# motorControl.net
KiCad netlist of a schematic drawn in EAGLE
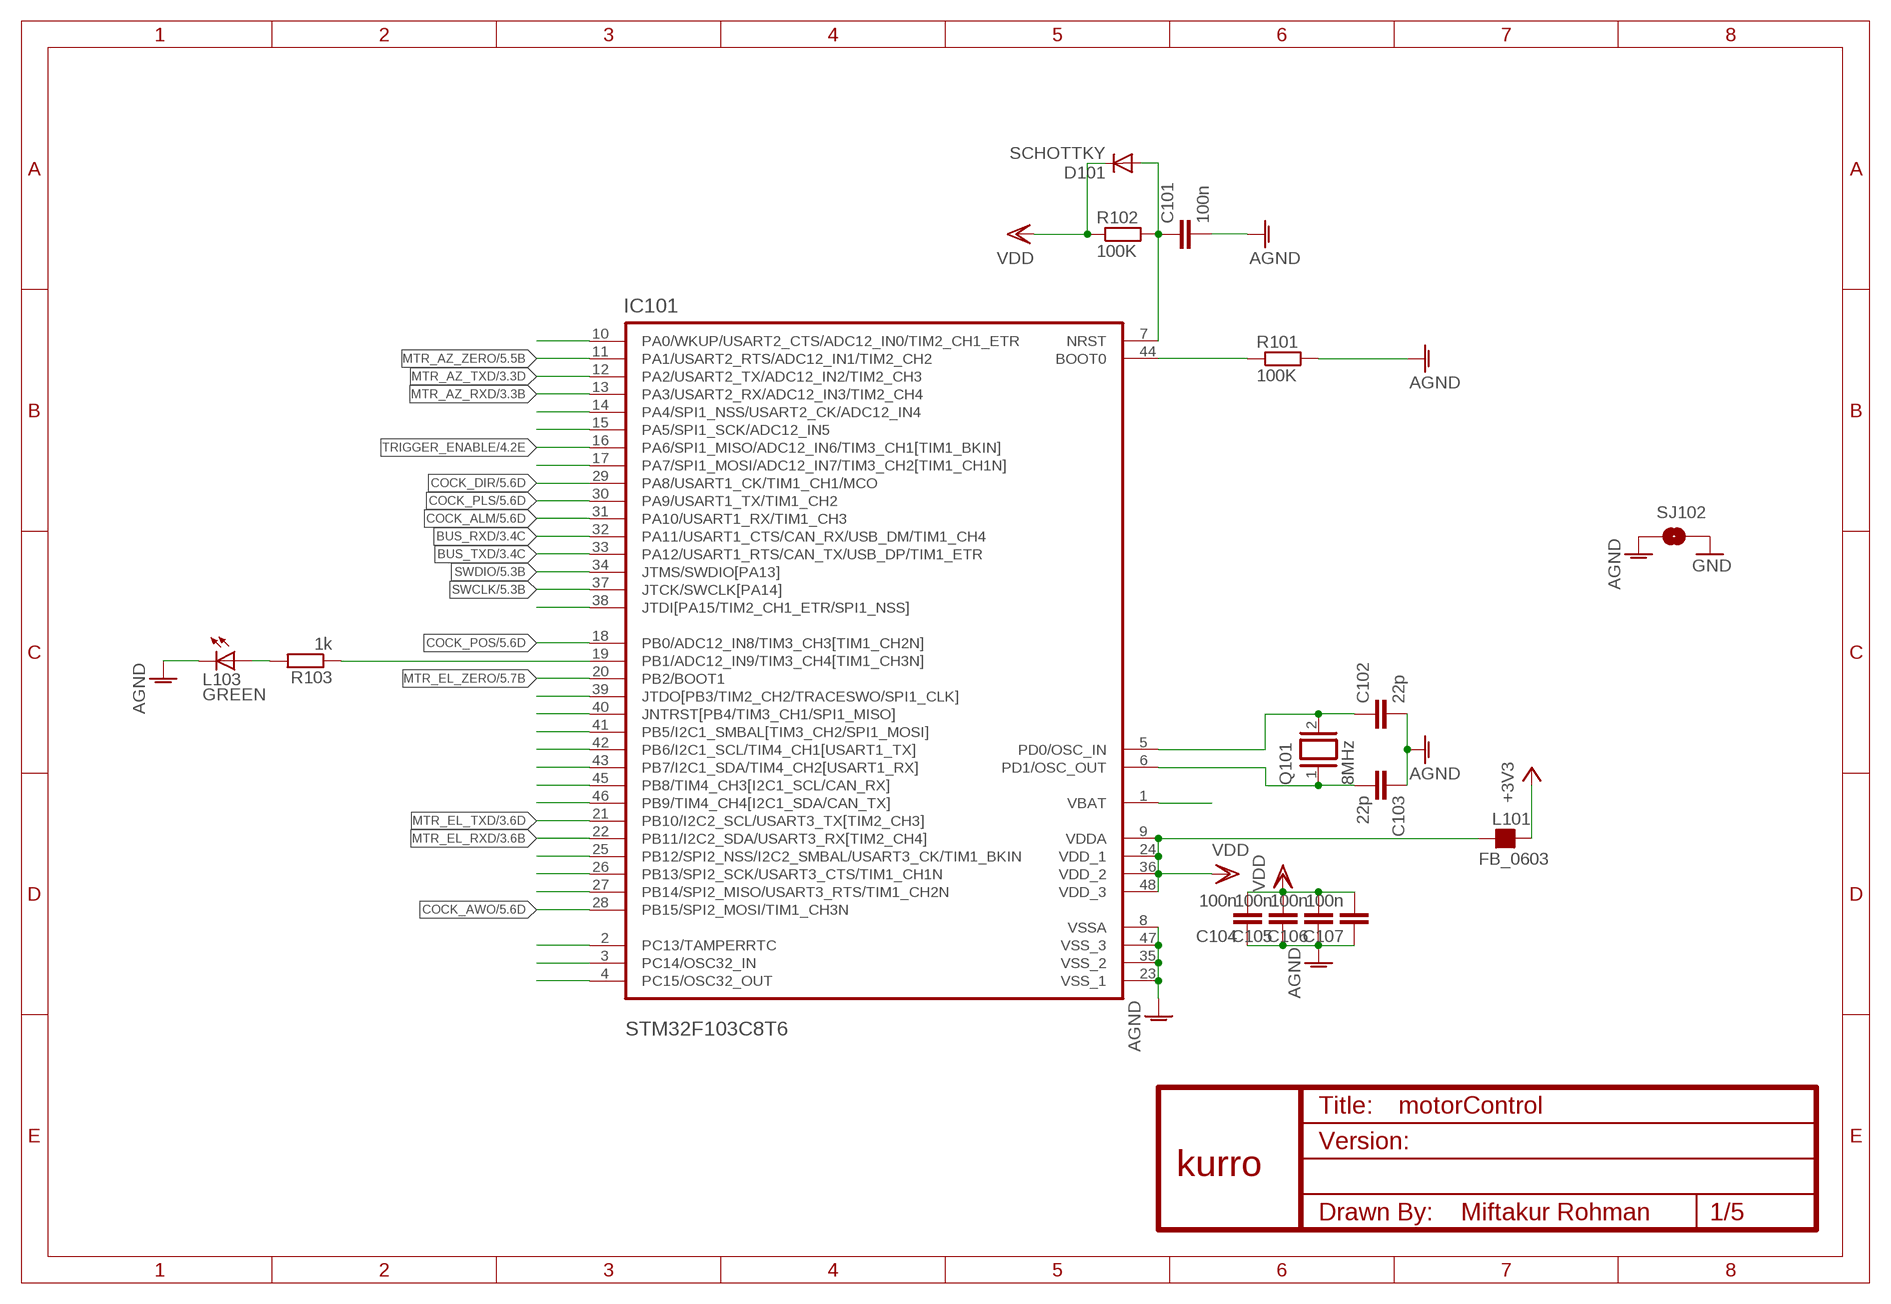
[diagram p0: schematic, sheet 1]
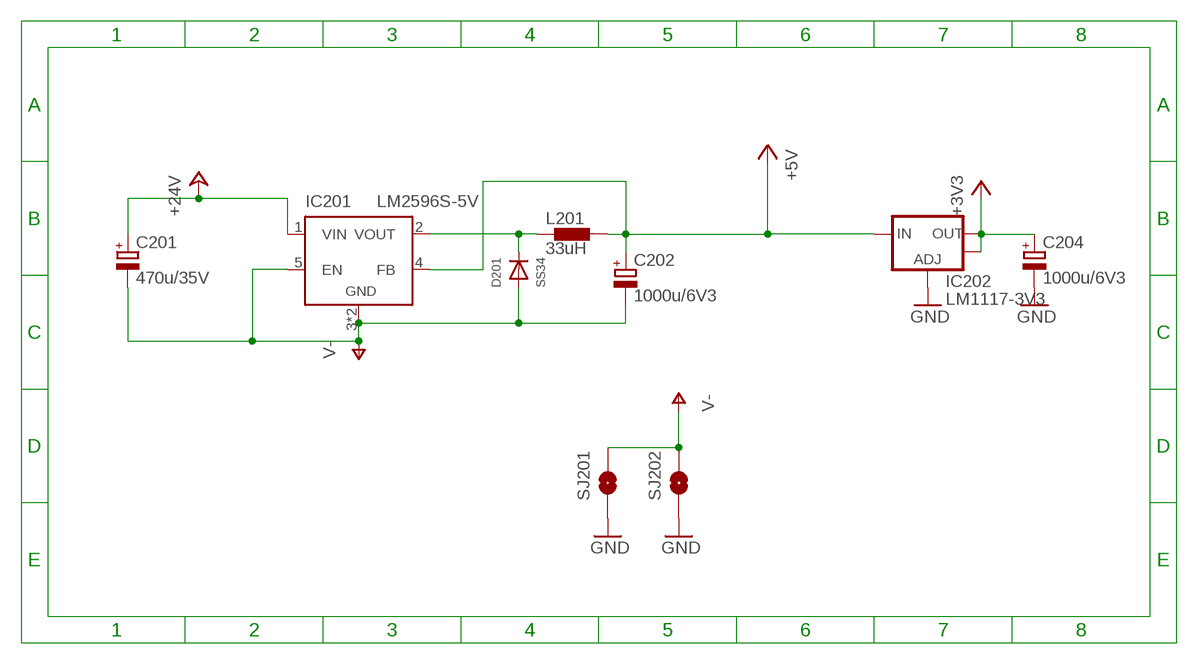
[diagram p1: schematic, sheet 2]
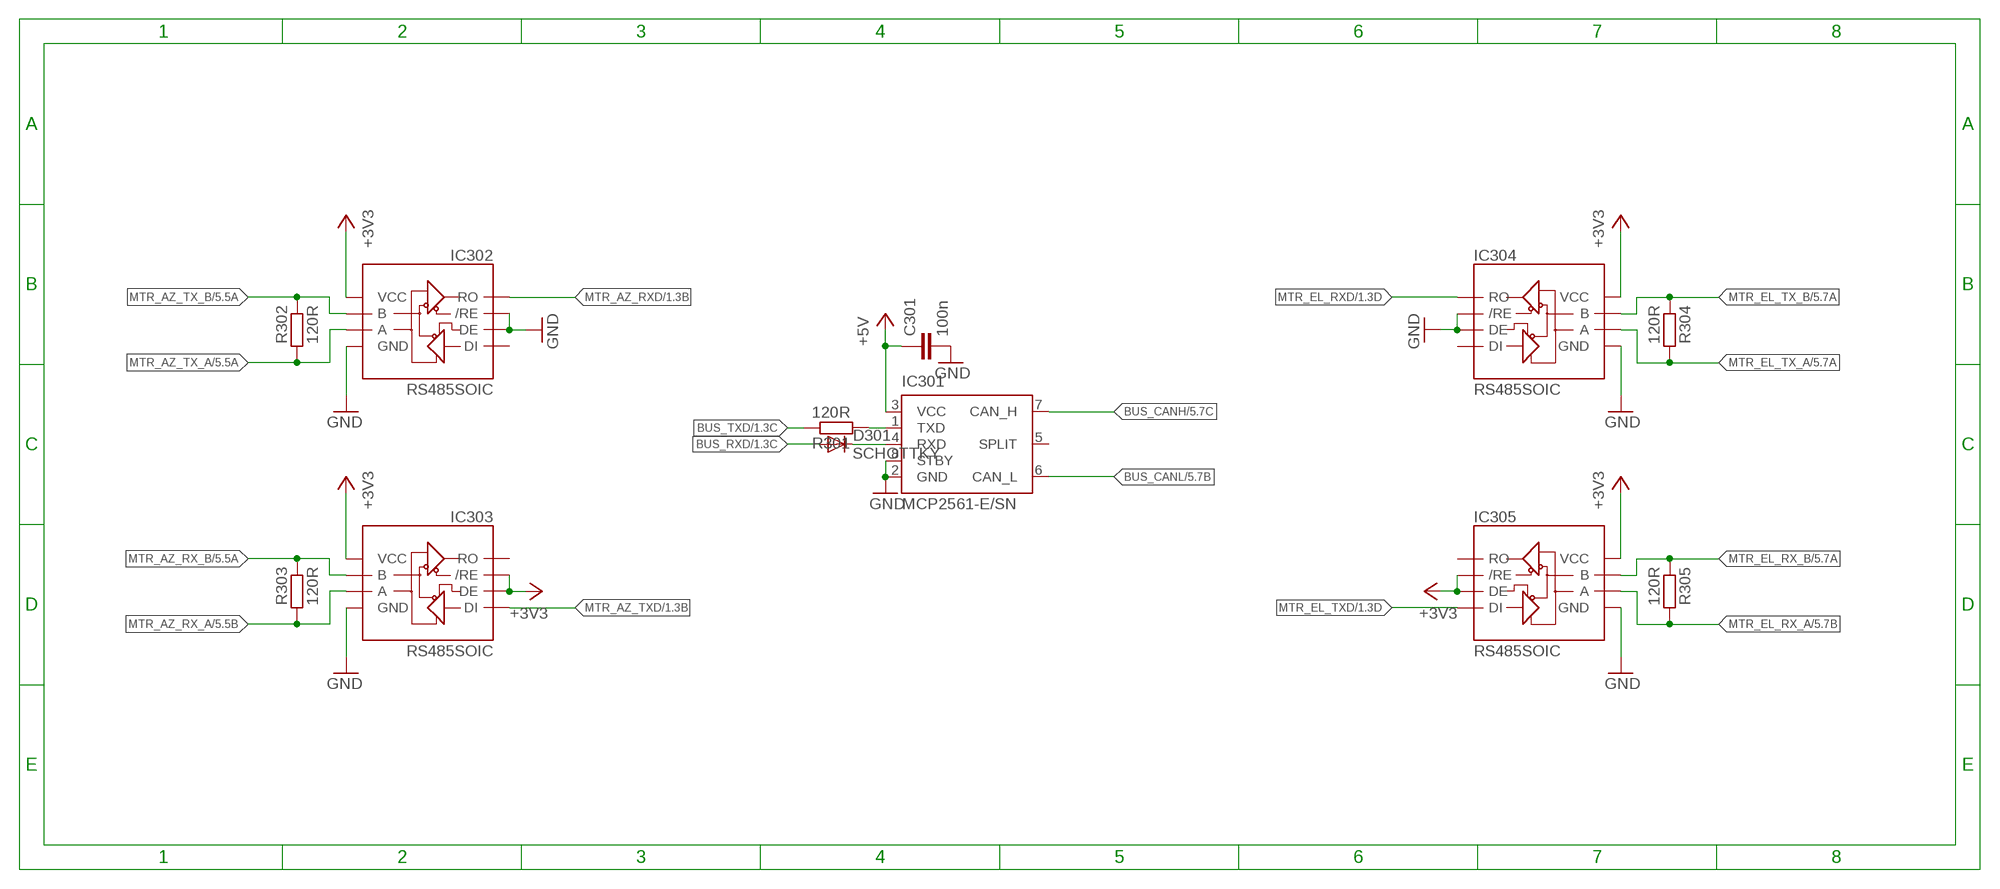
[diagram p2: schematic, sheet 3]
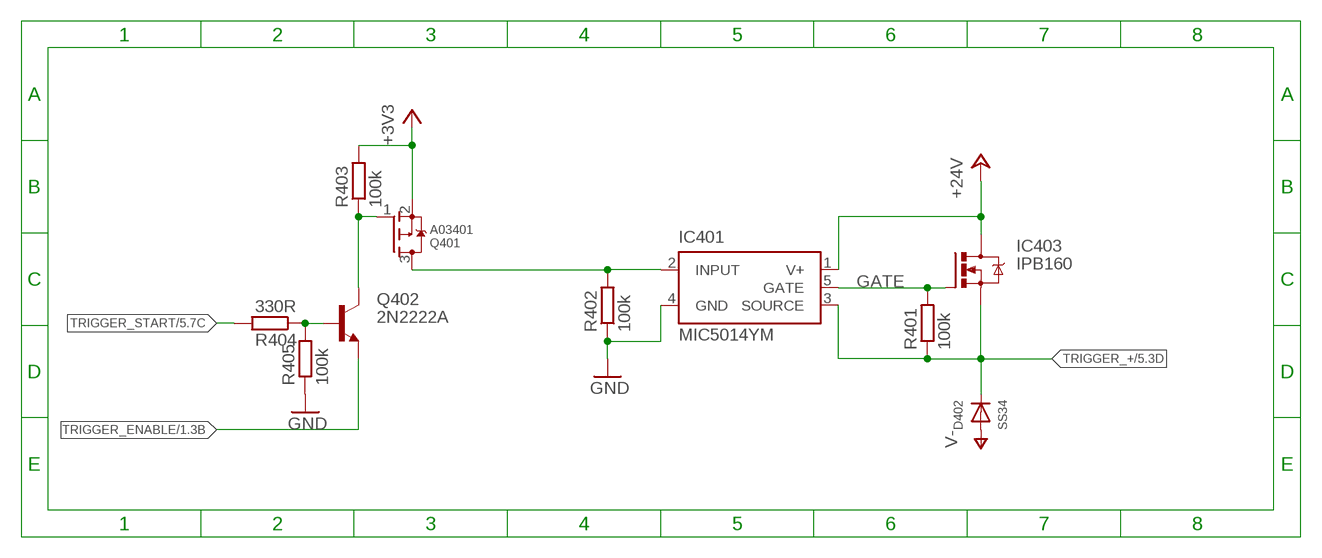
[diagram p3: schematic, sheet 4]
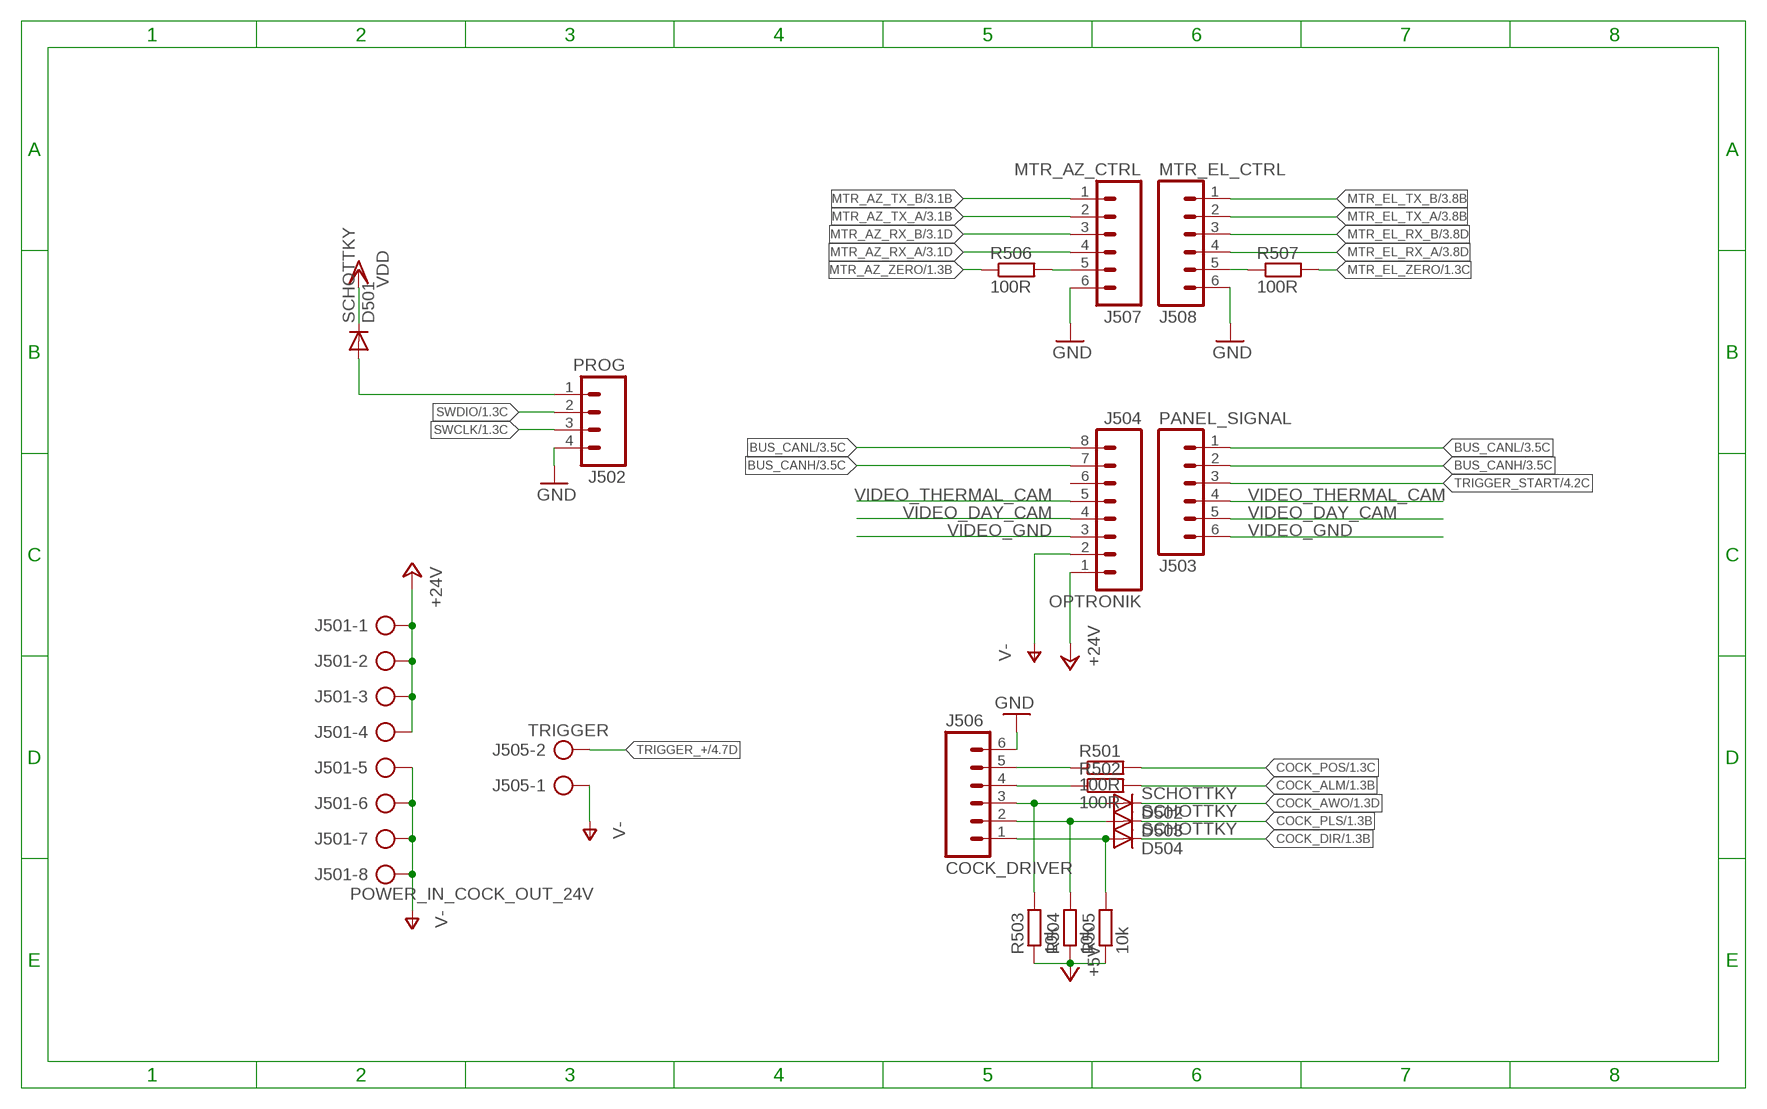
[diagram p4: schematic, sheet 5]

(export (version "E")
  (design (tool "Eeschema 10.0.6"))
  (components
    (comp (ref "C101")
      (value "100n")
      (footprint "eagle-import:C0603")
      (libsource (lib "eagle-import") (part "resistor_C-EUC0603"))
    )
    (comp (ref "C102")
      (value "22p")
      (footprint "eagle-import:C0603")
      (libsource (lib "eagle-import") (part "resistor_C-EUC0603"))
    )
    (comp (ref "C103")
      (value "22p")
      (footprint "eagle-import:C0603")
      (libsource (lib "eagle-import") (part "resistor_C-EUC0603"))
    )
    (comp (ref "C104")
      (value "100n")
      (footprint "eagle-import:C0603")
      (libsource (lib "eagle-import") (part "resistor_C-EUC0603"))
    )
    (comp (ref "C105")
      (value "100n")
      (footprint "eagle-import:C0603")
      (libsource (lib "eagle-import") (part "resistor_C-EUC0603"))
    )
    (comp (ref "C106")
      (value "100n")
      (footprint "eagle-import:C0603")
      (libsource (lib "eagle-import") (part "resistor_C-EUC0603"))
    )
    (comp (ref "C107")
      (value "100n")
      (footprint "eagle-import:C0603")
      (libsource (lib "eagle-import") (part "resistor_C-EUC0603"))
    )
    (comp (ref "D101")
      (value "SCHOTTKY")
      (footprint "eagle-import:MICROMELF-W")
      (libsource (lib "eagle-import") (part "DIODE-MICROMELF-W"))
    )
    (comp (ref "IC101")
      (value "STM32F103C8T6")
      (footprint "eagle-import:QFP50P900X900X160-48N")
      (fields (field (name "MPN") "STM32F103CBT6"))
      (libsource (lib "eagle-import") (part "STM32F103C8T6"))
    )
    (comp (ref "L101")
      (value "FB_0603")
      (footprint "eagle-import:L0603")
      (libsource (lib "eagle-import") (part "FB_0603"))
    )
    (comp (ref "L103")
      (value "GREEN")
      (footprint "eagle-import:CHIP-LED0805")
      (libsource (lib "eagle-import") (part "LEDCHIP-LED0805"))
    )
    (comp (ref "Q101")
      (value "8MHz")
      (footprint "eagle-import:QS")
      (libsource (lib "eagle-import") (part "XTAL/S"))
    )
    (comp (ref "R101")
      (value "100K")
      (footprint "eagle-import:R0603")
      (libsource (lib "eagle-import") (part "resistor_R-EU_R0603"))
    )
    (comp (ref "R102")
      (value "100K")
      (footprint "eagle-import:R0603")
      (libsource (lib "eagle-import") (part "resistor_R-EU_R0603"))
    )
    (comp (ref "R103")
      (value "1k")
      (footprint "eagle-import:R0603")
      (libsource (lib "eagle-import") (part "resistor_R-EU_R0603"))
    )
    (comp (ref "SJ102")
      (value "SOLDERJUMPERTRACE")
      (footprint "eagle-import:SJ_2S-TRACE")
      (libsource (lib "eagle-import") (part "SOLDERJUMPERTRACE"))
    )
    (comp (ref "U$1")
      (value "KURRO_FOOTPRINT")
      (footprint "eagle-import:KURRO-LOGO")
      (libsource (lib "eagle-import") (part "KURRO_FOOTPRINT"))
    )
    (comp (ref "C301")
      (value "100n")
      (footprint "eagle-import:C0603")
      (libsource (lib "eagle-import") (part "C-EUC0603"))
    )
    (comp (ref "D301")
      (value "SCHOTTKY")
      (footprint "eagle-import:MICROMELF-W")
      (libsource (lib "eagle-import") (part "DIODE-MICROMELF-W"))
    )
    (comp (ref "IC301")
      (value "MCP2561-E/SN")
      (footprint "eagle-import:SOIC-8")
      (libsource (lib "eagle-import") (part "MCP2561-E/SN"))
    )
    (comp (ref "IC302")
      (value "RS485SOIC")
      (footprint "eagle-import:SO08")
      (libsource (lib "eagle-import") (part "RS485SOIC"))
    )
    (comp (ref "IC303")
      (value "RS485SOIC")
      (footprint "eagle-import:SO08")
      (libsource (lib "eagle-import") (part "RS485SOIC"))
    )
    (comp (ref "IC304")
      (value "RS485SOIC")
      (footprint "eagle-import:SO08")
      (libsource (lib "eagle-import") (part "RS485SOIC"))
    )
    (comp (ref "IC305")
      (value "RS485SOIC")
      (footprint "eagle-import:SO08")
      (libsource (lib "eagle-import") (part "RS485SOIC"))
    )
    (comp (ref "R301")
      (value "120R")
      (footprint "eagle-import:R0603")
      (libsource (lib "eagle-import") (part "resistor_R-EU_R0603"))
    )
    (comp (ref "R302")
      (value "120R")
      (footprint "eagle-import:R0603")
      (libsource (lib "eagle-import") (part "resistor_R-EU_R0603"))
    )
    (comp (ref "R303")
      (value "120R")
      (footprint "eagle-import:R0603")
      (libsource (lib "eagle-import") (part "resistor_R-EU_R0603"))
    )
    (comp (ref "R304")
      (value "120R")
      (footprint "eagle-import:R0603")
      (libsource (lib "eagle-import") (part "resistor_R-EU_R0603"))
    )
    (comp (ref "R305")
      (value "120R")
      (footprint "eagle-import:R0603")
      (libsource (lib "eagle-import") (part "resistor_R-EU_R0603"))
    )
    (comp (ref "C201")
      (value "470u/35V")
      (footprint "eagle-import:153CLV-1012")
      (libsource (lib "eagle-import") (part "CPOL-EU153CLV-1012"))
    )
    (comp (ref "C202")
      (value "1000u/6V3")
      (footprint "eagle-import:153CLV-0810")
      (libsource (lib "eagle-import") (part "CPOL-EU153CLV-0810"))
    )
    (comp (ref "C204")
      (value "1000u/6V3")
      (footprint "eagle-import:153CLV-0810")
      (libsource (lib "eagle-import") (part "CPOL-EU153CLV-0810"))
    )
    (comp (ref "D201")
      (value "SS34")
      (footprint "eagle-import:SMADIODE")
      (libsource (lib "eagle-import") (part "DIODESMA"))
    )
    (comp (ref "IC201")
      (value "LM2596S-5V")
      (footprint "eagle-import:D2PAK")
      (libsource (lib "eagle-import") (part "LM2596S-ADJ"))
    )
    (comp (ref "IC202")
      (value "LM1117-3V3")
      (footprint "eagle-import:SOT223")
      (libsource (lib "eagle-import") (part "V_REG_LM1117SOT223"))
    )
    (comp (ref "L201")
      (value "33uH")
      (footprint "eagle-import:PA4342")
      (libsource (lib "eagle-import") (part "PA4342"))
    )
    (comp (ref "SJ201")
      (value "SOLDERJUMPERTRACE")
      (footprint "eagle-import:SJ_2S-TRACE")
      (libsource (lib "eagle-import") (part "SOLDERJUMPERTRACE"))
    )
    (comp (ref "SJ202")
      (value "SOLDERJUMPERTRACE")
      (footprint "eagle-import:SJ_2S-TRACE")
      (libsource (lib "eagle-import") (part "SOLDERJUMPERTRACE"))
    )
    (comp (ref "D402")
      (value "SS34")
      (footprint "eagle-import:SMADIODE")
      (libsource (lib "eagle-import") (part "DIODESMA"))
    )
    (comp (ref "IC401")
      (value "MIC5014YM")
      (footprint "eagle-import:SO-08")
      (libsource (lib "eagle-import") (part "MIC501M4Y"))
    )
    (comp (ref "IC403")
      (value "IPB160")
      (footprint "eagle-import:PG-TO263-7")
      (libsource (lib "eagle-import") (part "IPB160"))
    )
    (comp (ref "Q401")
      (value "A03401")
      (footprint "eagle-import:SOT23")
      (libsource (lib "eagle-import") (part "A03401-REFLOW"))
    )
    (comp (ref "Q402")
      (value "2N2222A")
      (footprint "eagle-import:SOT23")
      (libsource (lib "eagle-import") (part "2N2222-REFLOWA"))
    )
    (comp (ref "R401")
      (value "100k")
      (footprint "eagle-import:R0603")
      (libsource (lib "eagle-import") (part "R-EU_R0603"))
    )
    (comp (ref "R402")
      (value "100k")
      (footprint "eagle-import:R0603")
      (libsource (lib "eagle-import") (part "R-EU_R0603"))
    )
    (comp (ref "R403")
      (value "100k")
      (footprint "eagle-import:R0603")
      (libsource (lib "eagle-import") (part "R-EU_R0603"))
    )
    (comp (ref "R404")
      (value "330R")
      (footprint "eagle-import:R0603")
      (libsource (lib "eagle-import") (part "R-EU_R0603"))
    )
    (comp (ref "R405")
      (value "100k")
      (footprint "eagle-import:R0603")
      (libsource (lib "eagle-import") (part "R-EU_R0603"))
    )
    (comp (ref "D501")
      (value "SCHOTTKY")
      (footprint "eagle-import:MICROMELF-W")
      (libsource (lib "eagle-import") (part "DIODE-MICROMELF-W"))
    )
    (comp (ref "D502")
      (value "SCHOTTKY")
      (footprint "eagle-import:MICROMELF-W")
      (libsource (lib "eagle-import") (part "DIODE-MICROMELF-W"))
    )
    (comp (ref "D503")
      (value "SCHOTTKY")
      (footprint "eagle-import:MICROMELF-W")
      (libsource (lib "eagle-import") (part "DIODE-MICROMELF-W"))
    )
    (comp (ref "D504")
      (value "SCHOTTKY")
      (footprint "eagle-import:MICROMELF-W")
      (libsource (lib "eagle-import") (part "DIODE-MICROMELF-W"))
    )
    (comp (ref "J501")
      (value "POWER_IN_COCK_OUT_24V")
      (footprint "eagle-import:AK300_8")
      (libsource (lib "eagle-import") (part "AK300/8"))
    )
    (comp (ref "J502")
      (value "PROG")
      (footprint "eagle-import:XH-4-VERT-SMD")
      (libsource (lib "eagle-import") (part "M04-XH-VERT-SMD"))
    )
    (comp (ref "J503")
      (value "PANEL_SIGNAL")
      (footprint "eagle-import:XH-6-VERT-SMD")
      (libsource (lib "eagle-import") (part "M06-XH-VERT-SMD"))
    )
    (comp (ref "J504")
      (value "OPTRONIK")
      (footprint "eagle-import:XH-8-VERT-SMD")
      (libsource (lib "eagle-import") (part "M08-XH-VERT-SMD"))
    )
    (comp (ref "J505")
      (value "TRIGGER")
      (footprint "eagle-import:AK300_2")
      (libsource (lib "eagle-import") (part "AK300/2"))
    )
    (comp (ref "J506")
      (value "COCK_DRIVER")
      (footprint "eagle-import:XH-6-VERT-SMD")
      (libsource (lib "eagle-import") (part "M06-XH-VERT-SMD"))
    )
    (comp (ref "J507")
      (value "MTR_AZ_CTRL")
      (footprint "eagle-import:XH-6-VERT-SMD")
      (libsource (lib "eagle-import") (part "M06-XH-VERT-SMD"))
    )
    (comp (ref "J508")
      (value "MTR_EL_CTRL")
      (footprint "eagle-import:XH-6-VERT-SMD")
      (libsource (lib "eagle-import") (part "M06-XH-VERT-SMD"))
    )
    (comp (ref "R501")
      (value "100R")
      (footprint "eagle-import:R0603")
      (libsource (lib "eagle-import") (part "resistor_R-EU_R0603"))
    )
    (comp (ref "R502")
      (value "100R")
      (footprint "eagle-import:R0603")
      (libsource (lib "eagle-import") (part "resistor_R-EU_R0603"))
    )
    (comp (ref "R503")
      (value "10k")
      (footprint "eagle-import:R0603")
      (libsource (lib "eagle-import") (part "resistor_R-EU_R0603"))
    )
    (comp (ref "R504")
      (value "10k")
      (footprint "eagle-import:R0603")
      (libsource (lib "eagle-import") (part "resistor_R-EU_R0603"))
    )
    (comp (ref "R505")
      (value "10k")
      (footprint "eagle-import:R0603")
      (libsource (lib "eagle-import") (part "resistor_R-EU_R0603"))
    )
    (comp (ref "R506")
      (value "100R")
      (footprint "eagle-import:R0603")
      (libsource (lib "eagle-import") (part "resistor_R-EU_R0603"))
    )
    (comp (ref "R507")
      (value "100R")
      (footprint "eagle-import:R0603")
      (libsource (lib "eagle-import") (part "resistor_R-EU_R0603"))
    )
  )
  (nets
    (net (code "1") (name "+3V3") (class "Default")
      (node (ref "C204") (pin "+") (pinfunction "+_+") (pintype "passive"))
      (node (ref "IC202") (pin "2") (pinfunction "OUT_2") (pintype "power_in"))
      (node (ref "IC202") (pin "4") (pinfunction "OUT_4") (pintype "power_in"))
      (node (ref "IC302") (pin "8") (pinfunction "VCC_8") (pintype "bidirectional"))
      (node (ref "IC303") (pin "2") (pinfunction "/RE_2") (pintype "bidirectional"))
      (node (ref "IC303") (pin "3") (pinfunction "DE_3") (pintype "bidirectional"))
      (node (ref "IC303") (pin "8") (pinfunction "VCC_8") (pintype "bidirectional"))
      (node (ref "IC304") (pin "8") (pinfunction "VCC_8") (pintype "bidirectional"))
      (node (ref "IC305") (pin "2") (pinfunction "/RE_2") (pintype "bidirectional"))
      (node (ref "IC305") (pin "3") (pinfunction "DE_3") (pintype "bidirectional"))
      (node (ref "IC305") (pin "8") (pinfunction "VCC_8") (pintype "bidirectional"))
      (node (ref "L101") (pin "2") (pinfunction "2_2") (pintype "passive"))
      (node (ref "Q401") (pin "2") (pinfunction "S_2") (pintype "bidirectional"))
      (node (ref "R403") (pin "2") (pinfunction "2_2") (pintype "passive"))
    )
    (net (code "2") (name "+5V") (class "Default")
      (node (ref "C202") (pin "+") (pinfunction "+_+") (pintype "passive"))
      (node (ref "C301") (pin "1") (pinfunction "1_1") (pintype "passive"))
      (node (ref "IC201") (pin "4") (pinfunction "FB_4") (pintype "input"))
      (node (ref "IC202") (pin "3") (pinfunction "IN_3") (pintype "input"))
      (node (ref "IC301") (pin "3") (pinfunction "VCC_3") (pintype "bidirectional"))
      (node (ref "L201") (pin "P$2") (pinfunction "2_P$2") (pintype "passive"))
      (node (ref "R503") (pin "1") (pinfunction "1_1") (pintype "passive"))
      (node (ref "R504") (pin "1") (pinfunction "1_1") (pintype "passive"))
      (node (ref "R505") (pin "1") (pinfunction "1_1") (pintype "passive"))
    )
    (net (code "3") (name "+24V") (class "Default")
      (node (ref "C201") (pin "+") (pinfunction "+_+") (pintype "passive"))
      (node (ref "IC201") (pin "1") (pinfunction "VIN_1") (pintype "power_in"))
      (node (ref "IC401") (pin "1") (pinfunction "V+_1") (pintype "bidirectional"))
      (node (ref "IC403") (pin "4") (pinfunction "D_4") (pintype "passive"))
      (node (ref "J501") (pin "1") (pinfunction "KL_1") (pintype "passive"))
      (node (ref "J501") (pin "2") (pinfunction "KL_2") (pintype "passive"))
      (node (ref "J501") (pin "3") (pinfunction "KL_3") (pintype "passive"))
      (node (ref "J501") (pin "4") (pinfunction "KL_4") (pintype "passive"))
      (node (ref "J504") (pin "1") (pinfunction "1_1") (pintype "passive"))
    )
    (net (code "4") (name "AGND") (class "Default")
      (node (ref "C101") (pin "2") (pinfunction "2_2") (pintype "passive"))
      (node (ref "C102") (pin "2") (pinfunction "2_2") (pintype "passive"))
      (node (ref "C103") (pin "1") (pinfunction "1_1") (pintype "passive"))
      (node (ref "C104") (pin "1") (pinfunction "1_1") (pintype "passive"))
      (node (ref "C105") (pin "1") (pinfunction "1_1") (pintype "passive"))
      (node (ref "C106") (pin "1") (pinfunction "1_1") (pintype "passive"))
      (node (ref "C107") (pin "1") (pinfunction "1_1") (pintype "passive"))
      (node (ref "IC101") (pin "23") (pinfunction "VSS_1_23") (pintype "bidirectional"))
      (node (ref "IC101") (pin "35") (pinfunction "VSS_2_35") (pintype "passive"))
      (node (ref "IC101") (pin "47") (pinfunction "VSS_3_47") (pintype "passive"))
      (node (ref "IC101") (pin "8") (pinfunction "VSSA_8") (pintype "passive"))
      (node (ref "L103") (pin "C") (pinfunction "C_C") (pintype "passive"))
      (node (ref "R101") (pin "2") (pinfunction "2_2") (pintype "passive"))
      (node (ref "SJ102") (pin "1") (pinfunction "1_1") (pintype "passive"))
    )
    (net (code "5") (name "BUS_CANH") (class "Default")
      (node (ref "IC301") (pin "7") (pinfunction "CAN_H_7") (pintype "bidirectional"))
      (node (ref "J503") (pin "2") (pinfunction "2_2") (pintype "passive"))
      (node (ref "J504") (pin "7") (pinfunction "7_7") (pintype "passive"))
    )
    (net (code "6") (name "BUS_CANL") (class "Default")
      (node (ref "IC301") (pin "6") (pinfunction "CAN_L_6") (pintype "bidirectional"))
      (node (ref "J503") (pin "1") (pinfunction "1_1") (pintype "passive"))
      (node (ref "J504") (pin "8") (pinfunction "8_8") (pintype "passive"))
    )
    (net (code "7") (name "BUS_RXD") (class "Default")
      (node (ref "D301") (pin "A") (pinfunction "A_A") (pintype "passive"))
      (node (ref "IC101") (pin "32") (pinfunction "PA11/USART1_CTS/CAN_RX/USB_DM/TIM1_CH4_32") (pintype "power_in"))
    )
    (net (code "8") (name "BUS_TXD") (class "Default")
      (node (ref "IC101") (pin "33") (pinfunction "PA12/USART1_RTS/CAN_TX/USB_DP/TIM1_ETR_33") (pintype "bidirectional"))
      (node (ref "R301") (pin "1") (pinfunction "1_1") (pintype "passive"))
    )
    (net (code "9") (name "COCK_ALM") (class "Default")
      (node (ref "IC101") (pin "31") (pinfunction "PA10/USART1_RX/TIM1_CH3_31") (pintype "bidirectional"))
      (node (ref "R502") (pin "2") (pinfunction "2_2") (pintype "passive"))
    )
    (net (code "10") (name "COCK_AWO") (class "Default")
      (node (ref "D502") (pin "C") (pinfunction "C_C") (pintype "passive"))
      (node (ref "IC101") (pin "28") (pinfunction "PB15/SPI2_MOSI/TIM1_CH3N_28") (pintype "bidirectional"))
    )
    (net (code "11") (name "COCK_DIR") (class "Default")
      (node (ref "D504") (pin "C") (pinfunction "C_C") (pintype "passive"))
      (node (ref "IC101") (pin "29") (pinfunction "PA8/USART1_CK/TIM1_CH1/MCO_29") (pintype "bidirectional"))
    )
    (net (code "12") (name "COCK_PLS") (class "Default")
      (node (ref "D503") (pin "C") (pinfunction "C_C") (pintype "passive"))
      (node (ref "IC101") (pin "30") (pinfunction "PA9/USART1_TX/TIM1_CH2_30") (pintype "bidirectional"))
    )
    (net (code "13") (name "COCK_POS") (class "Default")
      (node (ref "IC101") (pin "18") (pinfunction "PB0/ADC12_IN8/TIM3_CH3[TIM1_CH2N]_18") (pintype "bidirectional"))
      (node (ref "R501") (pin "2") (pinfunction "2_2") (pintype "passive"))
    )
    (net (code "14") (name "GATE") (class "Default")
      (node (ref "IC401") (pin "5") (pinfunction "GATE_5") (pintype "bidirectional"))
      (node (ref "IC403") (pin "1") (pinfunction "G_1") (pintype "passive"))
      (node (ref "R401") (pin "2") (pinfunction "2_2") (pintype "passive"))
    )
    (net (code "15") (name "GND") (class "Default")
      (node (ref "C204") (pin "-") (pinfunction "-_-") (pintype "passive"))
      (node (ref "C301") (pin "2") (pinfunction "2_2") (pintype "passive"))
      (node (ref "IC202") (pin "1") (pinfunction "ADJ_1") (pintype "input"))
      (node (ref "IC301") (pin "2") (pinfunction "GND_2") (pintype "bidirectional"))
      (node (ref "IC301") (pin "8") (pinfunction "STBY_8") (pintype "bidirectional"))
      (node (ref "IC302") (pin "2") (pinfunction "/RE_2") (pintype "bidirectional"))
      (node (ref "IC302") (pin "3") (pinfunction "DE_3") (pintype "bidirectional"))
      (node (ref "IC302") (pin "5") (pinfunction "GND_5") (pintype "bidirectional"))
      (node (ref "IC303") (pin "5") (pinfunction "GND_5") (pintype "bidirectional"))
      (node (ref "IC304") (pin "2") (pinfunction "/RE_2") (pintype "bidirectional"))
      (node (ref "IC304") (pin "3") (pinfunction "DE_3") (pintype "bidirectional"))
      (node (ref "IC304") (pin "5") (pinfunction "GND_5") (pintype "bidirectional"))
      (node (ref "IC305") (pin "5") (pinfunction "GND_5") (pintype "bidirectional"))
      (node (ref "IC401") (pin "4") (pinfunction "GND_4") (pintype "bidirectional"))
      (node (ref "J502") (pin "4") (pinfunction "4_4") (pintype "passive"))
      (node (ref "J506") (pin "6") (pinfunction "6_6") (pintype "passive"))
      (node (ref "J507") (pin "6") (pinfunction "6_6") (pintype "passive"))
      (node (ref "J508") (pin "6") (pinfunction "6_6") (pintype "passive"))
      (node (ref "R402") (pin "1") (pinfunction "1_1") (pintype "passive"))
      (node (ref "R405") (pin "1") (pinfunction "1_1") (pintype "passive"))
      (node (ref "SJ102") (pin "2") (pinfunction "2_2") (pintype "passive"))
      (node (ref "SJ201") (pin "1") (pinfunction "1_1") (pintype "passive"))
      (node (ref "SJ202") (pin "1") (pinfunction "1_1") (pintype "passive"))
    )
    (net (code "16") (name "MTR_AZ_RXD") (class "Default")
      (node (ref "IC101") (pin "13") (pinfunction "PA3/USART2_RX/ADC12_IN3/TIM2_CH4_13") (pintype "bidirectional"))
      (node (ref "IC302") (pin "1") (pinfunction "RO_1") (pintype "bidirectional"))
    )
    (net (code "17") (name "MTR_AZ_RX_A") (class "Default")
      (node (ref "IC303") (pin "6") (pinfunction "A_6") (pintype "bidirectional"))
      (node (ref "J507") (pin "4") (pinfunction "4_4") (pintype "passive"))
      (node (ref "R303") (pin "2") (pinfunction "2_2") (pintype "passive"))
    )
    (net (code "18") (name "MTR_AZ_RX_B") (class "Default")
      (node (ref "IC303") (pin "7") (pinfunction "B_7") (pintype "bidirectional"))
      (node (ref "J507") (pin "3") (pinfunction "3_3") (pintype "passive"))
      (node (ref "R303") (pin "1") (pinfunction "1_1") (pintype "passive"))
    )
    (net (code "19") (name "MTR_AZ_TXD") (class "Default")
      (node (ref "IC101") (pin "12") (pinfunction "PA2/USART2_TX/ADC12_IN2/TIM2_CH3_12") (pintype "bidirectional"))
      (node (ref "IC303") (pin "4") (pinfunction "DI_4") (pintype "bidirectional"))
    )
    (net (code "20") (name "MTR_AZ_TX_A") (class "Default")
      (node (ref "IC302") (pin "6") (pinfunction "A_6") (pintype "bidirectional"))
      (node (ref "J507") (pin "2") (pinfunction "2_2") (pintype "passive"))
      (node (ref "R302") (pin "2") (pinfunction "2_2") (pintype "passive"))
    )
    (net (code "21") (name "MTR_AZ_TX_B") (class "Default")
      (node (ref "IC302") (pin "7") (pinfunction "B_7") (pintype "bidirectional"))
      (node (ref "J507") (pin "1") (pinfunction "1_1") (pintype "passive"))
      (node (ref "R302") (pin "1") (pinfunction "1_1") (pintype "passive"))
    )
    (net (code "22") (name "MTR_AZ_ZERO") (class "Default")
      (node (ref "IC101") (pin "11") (pinfunction "PA1/USART2_RTS/ADC12_IN1/TIM2_CH2_11") (pintype "bidirectional"))
      (node (ref "R506") (pin "1") (pinfunction "1_1") (pintype "passive"))
    )
    (net (code "23") (name "MTR_EL_RXD") (class "Default")
      (node (ref "IC101") (pin "22") (pinfunction "PB11/I2C2_SDA/USART3_RX[TIM2_CH4]_22") (pintype "bidirectional"))
      (node (ref "IC304") (pin "1") (pinfunction "RO_1") (pintype "bidirectional"))
    )
    (net (code "24") (name "MTR_EL_RX_A") (class "Default")
      (node (ref "IC305") (pin "6") (pinfunction "A_6") (pintype "bidirectional"))
      (node (ref "J508") (pin "4") (pinfunction "4_4") (pintype "passive"))
      (node (ref "R305") (pin "2") (pinfunction "2_2") (pintype "passive"))
    )
    (net (code "25") (name "MTR_EL_RX_B") (class "Default")
      (node (ref "IC305") (pin "7") (pinfunction "B_7") (pintype "bidirectional"))
      (node (ref "J508") (pin "3") (pinfunction "3_3") (pintype "passive"))
      (node (ref "R305") (pin "1") (pinfunction "1_1") (pintype "passive"))
    )
    (net (code "26") (name "MTR_EL_TXD") (class "Default")
      (node (ref "IC101") (pin "21") (pinfunction "PB10/I2C2_SCL/USART3_TX[TIM2_CH3]_21") (pintype "bidirectional"))
      (node (ref "IC305") (pin "4") (pinfunction "DI_4") (pintype "bidirectional"))
    )
    (net (code "27") (name "MTR_EL_TX_A") (class "Default")
      (node (ref "IC304") (pin "6") (pinfunction "A_6") (pintype "bidirectional"))
      (node (ref "J508") (pin "2") (pinfunction "2_2") (pintype "passive"))
      (node (ref "R304") (pin "2") (pinfunction "2_2") (pintype "passive"))
    )
    (net (code "28") (name "MTR_EL_TX_B") (class "Default")
      (node (ref "IC304") (pin "7") (pinfunction "B_7") (pintype "bidirectional"))
      (node (ref "J508") (pin "1") (pinfunction "1_1") (pintype "passive"))
      (node (ref "R304") (pin "1") (pinfunction "1_1") (pintype "passive"))
    )
    (net (code "29") (name "MTR_EL_ZERO") (class "Default")
      (node (ref "IC101") (pin "20") (pinfunction "PB2/BOOT1_20") (pintype "bidirectional"))
      (node (ref "R507") (pin "2") (pinfunction "2_2") (pintype "passive"))
    )
    (net (code "30") (name "Net-(D501-PadA)") (class "Default")
      (node (ref "D501") (pin "A") (pinfunction "A_A") (pintype "passive"))
      (node (ref "J502") (pin "1") (pinfunction "1_1") (pintype "passive"))
    )
    (net (code "31") (name "Net-(D502-PadA)") (class "Default")
      (node (ref "D502") (pin "A") (pinfunction "A_A") (pintype "passive"))
      (node (ref "J506") (pin "3") (pinfunction "3_3") (pintype "passive"))
      (node (ref "R503") (pin "2") (pinfunction "2_2") (pintype "passive"))
    )
    (net (code "32") (name "Net-(D503-PadA)") (class "Default")
      (node (ref "D503") (pin "A") (pinfunction "A_A") (pintype "passive"))
      (node (ref "J506") (pin "2") (pinfunction "2_2") (pintype "passive"))
      (node (ref "R504") (pin "2") (pinfunction "2_2") (pintype "passive"))
    )
    (net (code "33") (name "Net-(D504-PadA)") (class "Default")
      (node (ref "D504") (pin "A") (pinfunction "A_A") (pintype "passive"))
      (node (ref "J506") (pin "1") (pinfunction "1_1") (pintype "passive"))
      (node (ref "R505") (pin "2") (pinfunction "2_2") (pintype "passive"))
    )
    (net (code "34") (name "Net-(IC101-BOOT0)") (class "Default")
      (node (ref "IC101") (pin "44") (pinfunction "BOOT0_44") (pintype "bidirectional"))
      (node (ref "R101") (pin "1") (pinfunction "1_1") (pintype "passive"))
    )
    (net (code "35") (name "Net-(IC101-NRST)") (class "Default")
      (node (ref "C101") (pin "1") (pinfunction "1_1") (pintype "passive"))
      (node (ref "D101") (pin "A") (pinfunction "A_A") (pintype "passive"))
      (node (ref "IC101") (pin "7") (pinfunction "NRST_7") (pintype "bidirectional"))
      (node (ref "R102") (pin "2") (pinfunction "2_2") (pintype "passive"))
    )
    (net (code "36") (name "Net-(IC101-PB1{slash}ADC12_IN9{slash}TIM3_CH4[TIM1_CH3N])") (class "Default")
      (node (ref "IC101") (pin "19") (pinfunction "PB1/ADC12_IN9/TIM3_CH4[TIM1_CH3N]_19") (pintype "bidirectional"))
      (node (ref "R103") (pin "1") (pinfunction "1_1") (pintype "passive"))
    )
    (net (code "37") (name "Net-(IC101-PD0{slash}OSC_IN)") (class "Default")
      (node (ref "C102") (pin "1") (pinfunction "1_1") (pintype "passive"))
      (node (ref "IC101") (pin "5") (pinfunction "PD0/OSC_IN_5") (pintype "bidirectional"))
      (node (ref "Q101") (pin "2") (pinfunction "2_2") (pintype "passive"))
    )
    (net (code "38") (name "Net-(IC101-PD1{slash}OSC_OUT)") (class "Default")
      (node (ref "C103") (pin "2") (pinfunction "2_2") (pintype "passive"))
      (node (ref "IC101") (pin "6") (pinfunction "PD1/OSC_OUT_6") (pintype "bidirectional"))
      (node (ref "Q101") (pin "1") (pinfunction "1_1") (pintype "passive"))
    )
    (net (code "39") (name "Net-(IC201-VOUT)") (class "Default")
      (node (ref "D201") (pin "C") (pinfunction "C_C") (pintype "passive"))
      (node (ref "IC201") (pin "2") (pinfunction "VOUT_2") (pintype "output"))
      (node (ref "L201") (pin "P$1") (pinfunction "1_P$1") (pintype "passive"))
    )
    (net (code "40") (name "Net-(IC301-RXD)") (class "Default")
      (node (ref "D301") (pin "C") (pinfunction "C_C") (pintype "passive"))
      (node (ref "IC301") (pin "4") (pinfunction "RXD_4") (pintype "bidirectional"))
    )
    (net (code "41") (name "Net-(IC301-TXD)") (class "Default")
      (node (ref "IC301") (pin "1") (pinfunction "TXD_1") (pintype "bidirectional"))
      (node (ref "R301") (pin "2") (pinfunction "2_2") (pintype "passive"))
    )
    (net (code "42") (name "Net-(IC401-INPUT)") (class "Default")
      (node (ref "IC401") (pin "2") (pinfunction "INPUT_2") (pintype "bidirectional"))
      (node (ref "Q401") (pin "3") (pinfunction "D_3") (pintype "bidirectional"))
      (node (ref "R402") (pin "2") (pinfunction "2_2") (pintype "passive"))
    )
    (net (code "43") (name "Net-(J506-Pad4)") (class "Default")
      (node (ref "J506") (pin "4") (pinfunction "4_4") (pintype "passive"))
      (node (ref "R502") (pin "1") (pinfunction "1_1") (pintype "passive"))
    )
    (net (code "44") (name "Net-(J506-Pad5)") (class "Default")
      (node (ref "J506") (pin "5") (pinfunction "5_5") (pintype "passive"))
      (node (ref "R501") (pin "1") (pinfunction "1_1") (pintype "passive"))
    )
    (net (code "45") (name "Net-(J507-Pad5)") (class "Default")
      (node (ref "J507") (pin "5") (pinfunction "5_5") (pintype "passive"))
      (node (ref "R506") (pin "2") (pinfunction "2_2") (pintype "passive"))
    )
    (net (code "46") (name "Net-(J508-Pad5)") (class "Default")
      (node (ref "J508") (pin "5") (pinfunction "5_5") (pintype "passive"))
      (node (ref "R507") (pin "1") (pinfunction "1_1") (pintype "passive"))
    )
    (net (code "47") (name "Net-(L103-PadA)") (class "Default")
      (node (ref "L103") (pin "A") (pinfunction "A_A") (pintype "passive"))
      (node (ref "R103") (pin "2") (pinfunction "2_2") (pintype "passive"))
    )
    (net (code "48") (name "Net-(Q401-G)") (class "Default")
      (node (ref "Q401") (pin "1") (pinfunction "G_1") (pintype "bidirectional"))
      (node (ref "Q402") (pin "3") (pinfunction "C_3") (pintype "passive"))
      (node (ref "R403") (pin "1") (pinfunction "1_1") (pintype "passive"))
    )
    (net (code "49") (name "Net-(Q402-B)") (class "Default")
      (node (ref "Q402") (pin "1") (pinfunction "B_1") (pintype "passive"))
      (node (ref "R404") (pin "1") (pinfunction "1_1") (pintype "passive"))
      (node (ref "R405") (pin "2") (pinfunction "2_2") (pintype "passive"))
    )
    (net (code "50") (name "SWCLK") (class "Default")
      (node (ref "IC101") (pin "37") (pinfunction "JTCK/SWCLK[PA14]_37") (pintype "bidirectional"))
      (node (ref "J502") (pin "3") (pinfunction "3_3") (pintype "passive"))
    )
    (net (code "51") (name "SWDIO") (class "Default")
      (node (ref "IC101") (pin "34") (pinfunction "JTMS/SWDIO[PA13]_34") (pintype "bidirectional"))
      (node (ref "J502") (pin "2") (pinfunction "2_2") (pintype "passive"))
    )
    (net (code "52") (name "TRIGGER_+") (class "Default")
      (node (ref "D402") (pin "C") (pinfunction "C_C") (pintype "passive"))
      (node (ref "IC401") (pin "3") (pinfunction "SOURCE_3") (pintype "bidirectional"))
      (node (ref "IC403") (pin "2") (pinfunction "S_2") (pintype "passive"))
      (node (ref "IC403") (pin "3") (pinfunction "S_3") (pintype "passive"))
      (node (ref "IC403") (pin "5") (pinfunction "S_5") (pintype "passive"))
      (node (ref "IC403") (pin "6") (pinfunction "S_6") (pintype "passive"))
      (node (ref "IC403") (pin "7") (pinfunction "S_7") (pintype "passive"))
      (node (ref "J505") (pin "2") (pinfunction "KL_2") (pintype "passive"))
      (node (ref "R401") (pin "1") (pinfunction "1_1") (pintype "passive"))
    )
    (net (code "53") (name "TRIGGER_ENABLE") (class "Default")
      (node (ref "IC101") (pin "16") (pinfunction "PA6/SPI1_MISO/ADC12_IN6/TIM3_CH1[TIM1_BKIN]_16") (pintype "bidirectional"))
      (node (ref "Q402") (pin "2") (pinfunction "E_2") (pintype "passive"))
    )
    (net (code "54") (name "TRIGGER_START") (class "Default")
      (node (ref "J503") (pin "3") (pinfunction "3_3") (pintype "passive"))
      (node (ref "R404") (pin "2") (pinfunction "2_2") (pintype "passive"))
    )
    (net (code "55") (name "V-") (class "Default")
      (node (ref "C201") (pin "-") (pinfunction "-_-") (pintype "passive"))
      (node (ref "C202") (pin "-") (pinfunction "-_-") (pintype "passive"))
      (node (ref "D201") (pin "A") (pinfunction "A_A") (pintype "passive"))
      (node (ref "D402") (pin "A") (pinfunction "A_A") (pintype "passive"))
      (node (ref "IC201") (pin "3") (pinfunction "GND_3") (pintype "passive"))
      (node (ref "IC201") (pin "5") (pinfunction "EN_5") (pintype "input"))
      (node (ref "IC201") (pin "6") (pinfunction "GND_6") (pintype "passive"))
      (node (ref "J501") (pin "5") (pinfunction "KL_5") (pintype "passive"))
      (node (ref "J501") (pin "6") (pinfunction "KL_6") (pintype "passive"))
      (node (ref "J501") (pin "7") (pinfunction "KL_7") (pintype "passive"))
      (node (ref "J501") (pin "8") (pinfunction "KL_8") (pintype "passive"))
      (node (ref "J504") (pin "2") (pinfunction "2_2") (pintype "passive"))
      (node (ref "J505") (pin "1") (pinfunction "KL_1") (pintype "passive"))
      (node (ref "SJ201") (pin "2") (pinfunction "2_2") (pintype "passive"))
      (node (ref "SJ202") (pin "2") (pinfunction "2_2") (pintype "passive"))
    )
    (net (code "56") (name "VDD") (class "Default")
      (node (ref "C104") (pin "2") (pinfunction "2_2") (pintype "passive"))
      (node (ref "C105") (pin "2") (pinfunction "2_2") (pintype "passive"))
      (node (ref "C106") (pin "2") (pinfunction "2_2") (pintype "passive"))
      (node (ref "C107") (pin "2") (pinfunction "2_2") (pintype "passive"))
      (node (ref "D101") (pin "C") (pinfunction "C_C") (pintype "passive"))
      (node (ref "D501") (pin "C") (pinfunction "C_C") (pintype "passive"))
      (node (ref "IC101") (pin "24") (pinfunction "VDD_1_24") (pintype "bidirectional"))
      (node (ref "IC101") (pin "36") (pinfunction "VDD_2_36") (pintype "power_in"))
      (node (ref "IC101") (pin "48") (pinfunction "VDD_3_48") (pintype "power_in"))
      (node (ref "IC101") (pin "9") (pinfunction "VDDA_9") (pintype "power_in"))
      (node (ref "L101") (pin "1") (pinfunction "1_1") (pintype "passive"))
      (node (ref "R102") (pin "1") (pinfunction "1_1") (pintype "passive"))
    )
    (net (code "57") (name "VIDEO_DAY_CAM") (class "Default")
      (node (ref "J503") (pin "5") (pinfunction "5_5") (pintype "passive"))
      (node (ref "J504") (pin "4") (pinfunction "4_4") (pintype "passive"))
    )
    (net (code "58") (name "VIDEO_GND") (class "Default")
      (node (ref "J503") (pin "6") (pinfunction "6_6") (pintype "passive"))
      (node (ref "J504") (pin "3") (pinfunction "3_3") (pintype "passive"))
    )
    (net (code "59") (name "VIDEO_THERMAL_CAM") (class "Default")
      (node (ref "J503") (pin "4") (pinfunction "4_4") (pintype "passive"))
      (node (ref "J504") (pin "5") (pinfunction "5_5") (pintype "passive"))
    )
    (net (code "60") (name "unconnected-(IC101-JNTRST[PB4{slash}TIM3_CH1{slash}SPI1_MISO]-Pad40)") (class "Default")
      (node (ref "IC101") (pin "40") (pinfunction "JNTRST[PB4/TIM3_CH1/SPI1_MISO]_40") (pintype "bidirectional"))
    )
    (net (code "61") (name "unconnected-(IC101-JTDI[PA15{slash}TIM2_CH1_ETR{slash}SPI1_NSS]-Pad38)") (class "Default")
      (node (ref "IC101") (pin "38") (pinfunction "JTDI[PA15/TIM2_CH1_ETR/SPI1_NSS]_38") (pintype "bidirectional"))
    )
    (net (code "62") (name "unconnected-(IC101-JTDO[PB3{slash}TIM2_CH2{slash}TRACESWO{slash}SPI1_CLK]-Pad39)") (class "Default")
      (node (ref "IC101") (pin "39") (pinfunction "JTDO[PB3/TIM2_CH2/TRACESWO/SPI1_CLK]_39") (pintype "bidirectional"))
    )
    (net (code "63") (name "unconnected-(IC101-PA0{slash}WKUP{slash}USART2_CTS{slash}ADC12_IN0{slash}TIM2_CH1_ETR-Pad10)") (class "Default")
      (node (ref "IC101") (pin "10") (pinfunction "PA0/WKUP/USART2_CTS/ADC12_IN0/TIM2_CH1_ETR_10") (pintype "bidirectional"))
    )
    (net (code "64") (name "unconnected-(IC101-PA4{slash}SPI1_NSS{slash}USART2_CK{slash}ADC12_IN4-Pad14)") (class "Default")
      (node (ref "IC101") (pin "14") (pinfunction "PA4/SPI1_NSS/USART2_CK/ADC12_IN4_14") (pintype "bidirectional"))
    )
    (net (code "65") (name "unconnected-(IC101-PA5{slash}SPI1_SCK{slash}ADC12_IN5-Pad15)") (class "Default")
      (node (ref "IC101") (pin "15") (pinfunction "PA5/SPI1_SCK/ADC12_IN5_15") (pintype "bidirectional"))
    )
    (net (code "66") (name "unconnected-(IC101-PA7{slash}SPI1_MOSI{slash}ADC12_IN7{slash}TIM3_CH2[TIM1_CH1N]-Pad17)") (class "Default")
      (node (ref "IC101") (pin "17") (pinfunction "PA7/SPI1_MOSI/ADC12_IN7/TIM3_CH2[TIM1_CH1N]_17") (pintype "bidirectional"))
    )
    (net (code "67") (name "unconnected-(IC101-PB5{slash}I2C1_SMBAL[TIM3_CH2{slash}SPI1_MOSI]-Pad41)") (class "Default")
      (node (ref "IC101") (pin "41") (pinfunction "PB5/I2C1_SMBAL[TIM3_CH2/SPI1_MOSI]_41") (pintype "bidirectional"))
    )
    (net (code "68") (name "unconnected-(IC101-PB6{slash}I2C1_SCL{slash}TIM4_CH1[USART1_TX]-Pad42)") (class "Default")
      (node (ref "IC101") (pin "42") (pinfunction "PB6/I2C1_SCL/TIM4_CH1[USART1_TX]_42") (pintype "bidirectional"))
    )
    (net (code "69") (name "unconnected-(IC101-PB7{slash}I2C1_SDA{slash}TIM4_CH2[USART1_RX]-Pad43)") (class "Default")
      (node (ref "IC101") (pin "43") (pinfunction "PB7/I2C1_SDA/TIM4_CH2[USART1_RX]_43") (pintype "bidirectional"))
    )
    (net (code "70") (name "unconnected-(IC101-PB8{slash}TIM4_CH3[I2C1_SCL{slash}CAN_RX]-Pad45)") (class "Default")
      (node (ref "IC101") (pin "45") (pinfunction "PB8/TIM4_CH3[I2C1_SCL/CAN_RX]_45") (pintype "bidirectional"))
    )
    (net (code "71") (name "unconnected-(IC101-PB9{slash}TIM4_CH4[I2C1_SDA{slash}CAN_TX]-Pad46)") (class "Default")
      (node (ref "IC101") (pin "46") (pinfunction "PB9/TIM4_CH4[I2C1_SDA/CAN_TX]_46") (pintype "bidirectional"))
    )
    (net (code "72") (name "unconnected-(IC101-PB12{slash}SPI2_NSS{slash}I2C2_SMBAL{slash}USART3_CK{slash}TIM1_BKIN-Pad25)") (class "Default")
      (node (ref "IC101") (pin "25") (pinfunction "PB12/SPI2_NSS/I2C2_SMBAL/USART3_CK/TIM1_BKIN_25") (pintype "bidirectional"))
    )
    (net (code "73") (name "unconnected-(IC101-PB13{slash}SPI2_SCK{slash}USART3_CTS{slash}TIM1_CH1N-Pad26)") (class "Default")
      (node (ref "IC101") (pin "26") (pinfunction "PB13/SPI2_SCK/USART3_CTS/TIM1_CH1N_26") (pintype "bidirectional"))
    )
    (net (code "74") (name "unconnected-(IC101-PB14{slash}SPI2_MISO{slash}USART3_RTS{slash}TIM1_CH2N-Pad27)") (class "Default")
      (node (ref "IC101") (pin "27") (pinfunction "PB14/SPI2_MISO/USART3_RTS/TIM1_CH2N_27") (pintype "bidirectional"))
    )
    (net (code "75") (name "unconnected-(IC101-PC13{slash}TAMPERRTC-Pad2)") (class "Default")
      (node (ref "IC101") (pin "2") (pinfunction "PC13/TAMPERRTC_2") (pintype "bidirectional"))
    )
    (net (code "76") (name "unconnected-(IC101-PC14{slash}OSC32_IN-Pad3)") (class "Default")
      (node (ref "IC101") (pin "3") (pinfunction "PC14/OSC32_IN_3") (pintype "bidirectional"))
    )
    (net (code "77") (name "unconnected-(IC101-PC15{slash}OSC32_OUT-Pad4)") (class "Default")
      (node (ref "IC101") (pin "4") (pinfunction "PC15/OSC32_OUT_4") (pintype "bidirectional"))
    )
    (net (code "78") (name "unconnected-(IC101-VBAT-Pad1)") (class "Default")
      (node (ref "IC101") (pin "1") (pinfunction "VBAT_1") (pintype "input"))
    )
    (net (code "79") (name "unconnected-(IC301-SPLIT-Pad5)") (class "Default")
      (node (ref "IC301") (pin "5") (pinfunction "SPLIT_5") (pintype "bidirectional"))
    )
    (net (code "80") (name "unconnected-(IC302-DI-Pad4)") (class "Default")
      (node (ref "IC302") (pin "4") (pinfunction "DI_4") (pintype "bidirectional"))
    )
    (net (code "81") (name "unconnected-(IC303-RO-Pad1)") (class "Default")
      (node (ref "IC303") (pin "1") (pinfunction "RO_1") (pintype "bidirectional"))
    )
    (net (code "82") (name "unconnected-(IC304-DI-Pad4)") (class "Default")
      (node (ref "IC304") (pin "4") (pinfunction "DI_4") (pintype "bidirectional"))
    )
    (net (code "83") (name "unconnected-(IC305-RO-Pad1)") (class "Default")
      (node (ref "IC305") (pin "1") (pinfunction "RO_1") (pintype "bidirectional"))
    )
    (net (code "84") (name "unconnected-(J504-Pad6)") (class "Default")
      (node (ref "J504") (pin "6") (pinfunction "6_6") (pintype "passive"))
    )
  )
)
